# IOs.net
KiCad netlist of a schematic drawn in Altium Designer
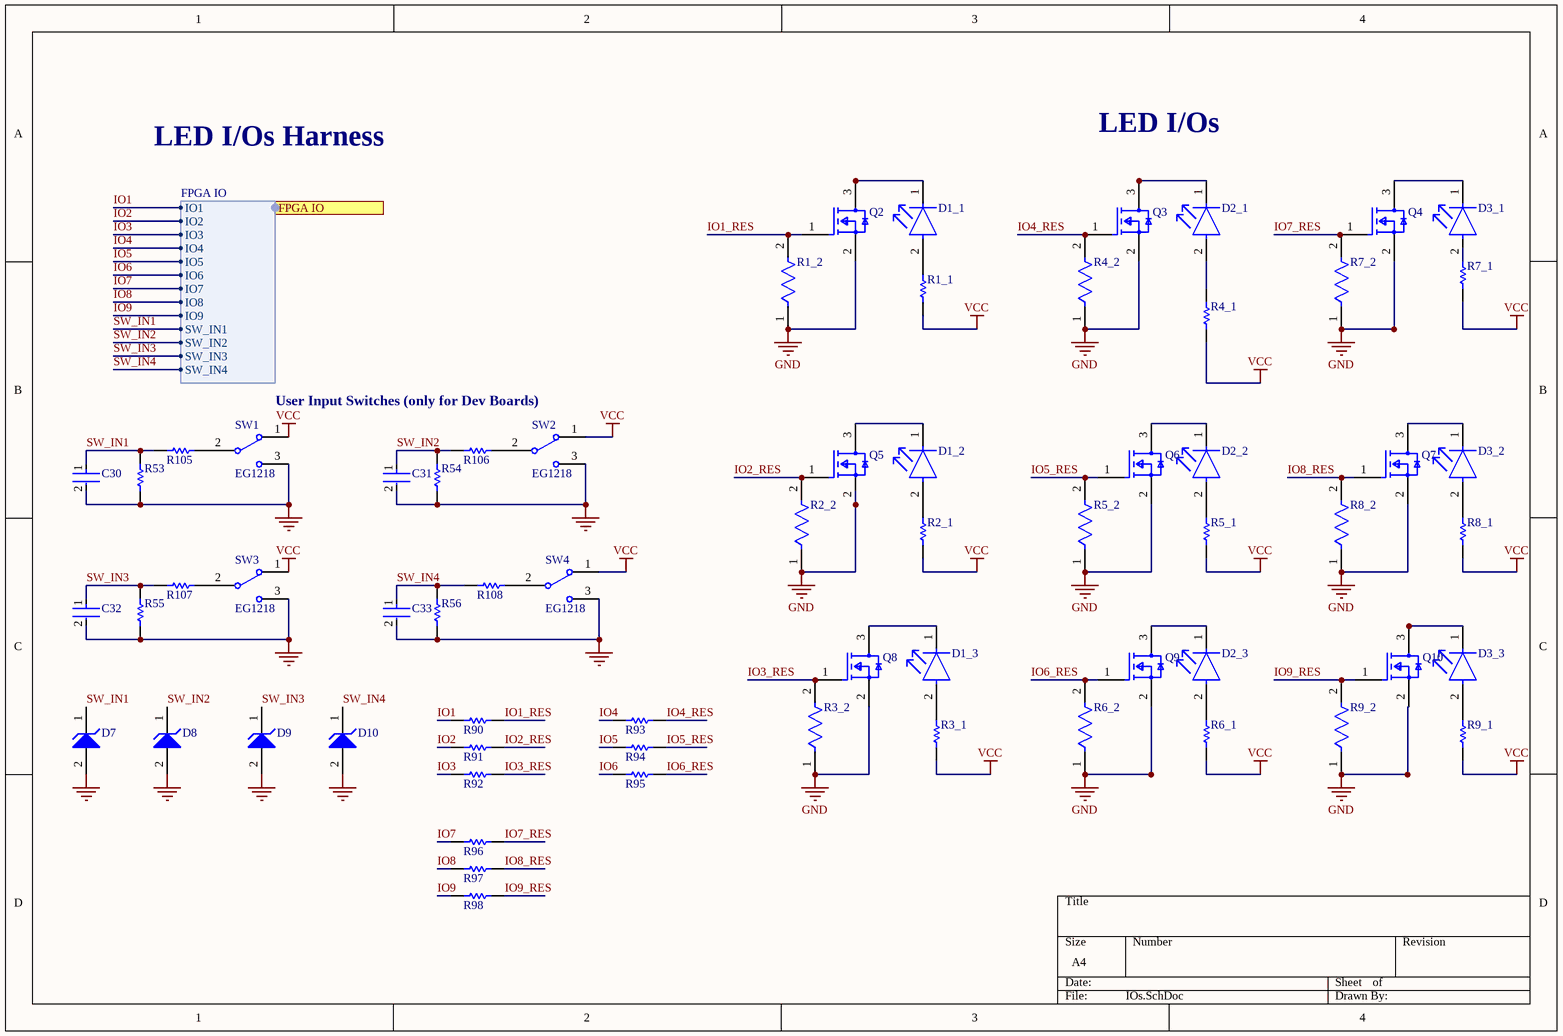
[diagram p0: IOs.SchDoc]

(export (version "E")
  (design (tool "Eeschema 10.0.6"))
  (components
    (comp (ref "C30")
      (value "CC0402KRX7R9BB103")
      (footprint "FP-CC0402-MFG")
      (description "CAP CER 10000PF 50V X7R 0402")
      (fields
        (field (name "OCTOPART") "https://octopart.com/cc0402krx7r9bb103-yageo-8376513")
        (field (name "MANUFACTURER") "YAGEO")
      )
      (libsource (lib "Altium Content Vault") (part "11868f565c42a9108669ba33697ecf6"))
    )
    (comp (ref "C31")
      (value "CC0402KRX7R9BB103")
      (footprint "FP-CC0402-MFG")
      (description "CAP CER 10000PF 50V X7R 0402")
      (fields
        (field (name "OCTOPART") "https://octopart.com/cc0402krx7r9bb103-yageo-8376513")
        (field (name "MANUFACTURER") "YAGEO")
      )
      (libsource (lib "Altium Content Vault") (part "11868f565c42a9108669ba33697ecf6"))
    )
    (comp (ref "C32")
      (value "CC0402KRX7R9BB103")
      (footprint "FP-CC0402-MFG")
      (description "CAP CER 10000PF 50V X7R 0402")
      (fields
        (field (name "OCTOPART") "https://octopart.com/cc0402krx7r9bb103-yageo-8376513")
        (field (name "MANUFACTURER") "YAGEO")
      )
      (libsource (lib "Altium Content Vault") (part "11868f565c42a9108669ba33697ecf6"))
    )
    (comp (ref "C33")
      (value "CC0402KRX7R9BB103")
      (footprint "FP-CC0402-MFG")
      (description "CAP CER 10000PF 50V X7R 0402")
      (fields
        (field (name "OCTOPART") "https://octopart.com/cc0402krx7r9bb103-yageo-8376513")
        (field (name "MANUFACTURER") "YAGEO")
      )
      (libsource (lib "Altium Content Vault") (part "11868f565c42a9108669ba33697ecf6"))
    )
    (comp (ref "D1_1")
      (value "LTST-C230KRKT")
      (footprint "FP-LTST-C230KRKT-MFG")
      (description "LED RED CLEAR CHIP SMD")
      (libsource (lib "Altium Content Vault") (part "8706943c75ba83719d021d2fdc84c58"))
    )
    (comp (ref "D1_2")
      (value "LTST-C230KRKT")
      (footprint "FP-LTST-C230KRKT-MFG")
      (description "LED RED CLEAR CHIP SMD")
      (libsource (lib "Altium Content Vault") (part "8706943c75ba83719d021d2fdc84c58"))
    )
    (comp (ref "D1_3")
      (value "LTST-C230KRKT")
      (footprint "FP-LTST-C230KRKT-MFG")
      (description "LED RED CLEAR CHIP SMD")
      (libsource (lib "Altium Content Vault") (part "8706943c75ba83719d021d2fdc84c58"))
    )
    (comp (ref "D2_1")
      (value "LTST-C230KRKT")
      (footprint "FP-LTST-C230KRKT-MFG")
      (description "LED RED CLEAR CHIP SMD")
      (libsource (lib "Altium Content Vault") (part "8706943c75ba83719d021d2fdc84c58"))
    )
    (comp (ref "D2_2")
      (value "LTST-C230KRKT")
      (footprint "FP-LTST-C230KRKT-MFG")
      (description "LED RED CLEAR CHIP SMD")
      (libsource (lib "Altium Content Vault") (part "8706943c75ba83719d021d2fdc84c58"))
    )
    (comp (ref "D2_3")
      (value "LTST-C230KRKT")
      (footprint "FP-LTST-C230KRKT-MFG")
      (description "LED RED CLEAR CHIP SMD")
      (libsource (lib "Altium Content Vault") (part "8706943c75ba83719d021d2fdc84c58"))
    )
    (comp (ref "D3_1")
      (value "LTST-C230KRKT")
      (footprint "FP-LTST-C230KRKT-MFG")
      (description "LED RED CLEAR CHIP SMD")
      (libsource (lib "Altium Content Vault") (part "8706943c75ba83719d021d2fdc84c58"))
    )
    (comp (ref "D3_2")
      (value "LTST-C230KRKT")
      (footprint "FP-LTST-C230KRKT-MFG")
      (description "LED RED CLEAR CHIP SMD")
      (libsource (lib "Altium Content Vault") (part "8706943c75ba83719d021d2fdc84c58"))
    )
    (comp (ref "D3_3")
      (value "LTST-C230KRKT")
      (footprint "FP-LTST-C230KRKT-MFG")
      (description "LED RED CLEAR CHIP SMD")
      (libsource (lib "Altium Content Vault") (part "8706943c75ba83719d021d2fdc84c58"))
    )
    (comp (ref "D7")
      (value "MM5Z3V3T1G")
      (footprint "ONSC-SOD-523-2-502-01_V")
      (description "Zener Voltage Regulator, 500 mW, 2-Pin SOD-523, Pb-Free, Tape and Reel")
      (fields (field (name "MANUFACTURER") "On Semiconductor"))
      (libsource (lib "Altium Content Vault") (part "ONSC-K1A2-2"))
    )
    (comp (ref "D8")
      (value "MM5Z3V3T1G")
      (footprint "ONSC-SOD-523-2-502-01_V")
      (description "Zener Voltage Regulator, 500 mW, 2-Pin SOD-523, Pb-Free, Tape and Reel")
      (fields (field (name "MANUFACTURER") "On Semiconductor"))
      (libsource (lib "Altium Content Vault") (part "ONSC-K1A2-2"))
    )
    (comp (ref "D9")
      (value "MM5Z3V3T1G")
      (footprint "ONSC-SOD-523-2-502-01_V")
      (description "Zener Voltage Regulator, 500 mW, 2-Pin SOD-523, Pb-Free, Tape and Reel")
      (fields (field (name "MANUFACTURER") "On Semiconductor"))
      (libsource (lib "Altium Content Vault") (part "ONSC-K1A2-2"))
    )
    (comp (ref "D10")
      (value "MM5Z3V3T1G")
      (footprint "ONSC-SOD-523-2-502-01_V")
      (description "Zener Voltage Regulator, 500 mW, 2-Pin SOD-523, Pb-Free, Tape and Reel")
      (fields (field (name "MANUFACTURER") "On Semiconductor"))
      (libsource (lib "Altium Content Vault") (part "ONSC-K1A2-2"))
    )
    (comp (ref "Q2")
      (value "MMBF170LT1G")
      (footprint "FP-318-08-IPC_B")
      (description "MOSFET N-CH 60V 500MA SOT-23")
      (libsource (lib "Altium Content Vault") (part "0a9ea7c96deaaede766a5b531c28de0"))
    )
    (comp (ref "Q3")
      (value "MMBF170LT1G")
      (footprint "FP-318-08-IPC_B")
      (description "MOSFET N-CH 60V 500MA SOT-23")
      (libsource (lib "Altium Content Vault") (part "0a9ea7c96deaaede766a5b531c28de0"))
    )
    (comp (ref "Q4")
      (value "MMBF170LT1G")
      (footprint "FP-318-08-IPC_B")
      (description "MOSFET N-CH 60V 500MA SOT-23")
      (libsource (lib "Altium Content Vault") (part "0a9ea7c96deaaede766a5b531c28de0"))
    )
    (comp (ref "Q5")
      (value "MMBF170LT1G")
      (footprint "FP-318-08-IPC_B")
      (description "MOSFET N-CH 60V 500MA SOT-23")
      (libsource (lib "Altium Content Vault") (part "0a9ea7c96deaaede766a5b531c28de0"))
    )
    (comp (ref "Q6")
      (value "MMBF170LT1G")
      (footprint "FP-318-08-IPC_B")
      (description "MOSFET N-CH 60V 500MA SOT-23")
      (libsource (lib "Altium Content Vault") (part "0a9ea7c96deaaede766a5b531c28de0"))
    )
    (comp (ref "Q7")
      (value "MMBF170LT1G")
      (footprint "FP-318-08-IPC_B")
      (description "MOSFET N-CH 60V 500MA SOT-23")
      (libsource (lib "Altium Content Vault") (part "0a9ea7c96deaaede766a5b531c28de0"))
    )
    (comp (ref "Q8")
      (value "MMBF170LT1G")
      (footprint "FP-318-08-IPC_B")
      (description "MOSFET N-CH 60V 500MA SOT-23")
      (libsource (lib "Altium Content Vault") (part "0a9ea7c96deaaede766a5b531c28de0"))
    )
    (comp (ref "Q9")
      (value "MMBF170LT1G")
      (footprint "FP-318-08-IPC_B")
      (description "MOSFET N-CH 60V 500MA SOT-23")
      (libsource (lib "Altium Content Vault") (part "0a9ea7c96deaaede766a5b531c28de0"))
    )
    (comp (ref "Q10")
      (value "MMBF170LT1G")
      (footprint "FP-318-08-IPC_B")
      (description "MOSFET N-CH 60V 500MA SOT-23")
      (libsource (lib "Altium Content Vault") (part "0a9ea7c96deaaede766a5b531c28de0"))
    )
    (comp (ref "R1_1")
      (value "RC0402FR-07330RL")
      (footprint "RESC1005X40X25LL05T10")
      (fields (field (name "MANUFACTURER") "Yageo / Phycomp"))
      (libsource (lib "Altium Content Vault") (part "RES"))
    )
    (comp (ref "R1_2")
      (value "RC0402JR-0710KL")
      (footprint "FP-RC0402-0_4-IPC_C")
      (description "RES 10K OHM 5% 1/16W 0402")
      (fields (field (name "TOLERANCE") "5%"))
      (libsource (lib "Altium Content Vault") (part "1029c3af85768c4190bb7ad29bc67b5"))
    )
    (comp (ref "R2_1")
      (value "RC0402FR-07330RL")
      (footprint "RESC1005X40X25LL05T10")
      (fields (field (name "MANUFACTURER") "Yageo / Phycomp"))
      (libsource (lib "Altium Content Vault") (part "RES"))
    )
    (comp (ref "R2_2")
      (value "RC0402JR-0710KL")
      (footprint "FP-RC0402-0_4-IPC_C")
      (description "RES 10K OHM 5% 1/16W 0402")
      (fields (field (name "TOLERANCE") "5%"))
      (libsource (lib "Altium Content Vault") (part "1029c3af85768c4190bb7ad29bc67b5"))
    )
    (comp (ref "R3_1")
      (value "RC0402FR-07330RL")
      (footprint "RESC1005X40X25LL05T10")
      (fields (field (name "MANUFACTURER") "Yageo / Phycomp"))
      (libsource (lib "Altium Content Vault") (part "RES"))
    )
    (comp (ref "R3_2")
      (value "RC0402JR-0710KL")
      (footprint "FP-RC0402-0_4-IPC_C")
      (description "RES 10K OHM 5% 1/16W 0402")
      (fields (field (name "TOLERANCE") "5%"))
      (libsource (lib "Altium Content Vault") (part "1029c3af85768c4190bb7ad29bc67b5"))
    )
    (comp (ref "R4_1")
      (value "RC0402FR-07330RL")
      (footprint "RESC1005X40X25LL05T10")
      (fields (field (name "MANUFACTURER") "Yageo / Phycomp"))
      (libsource (lib "Altium Content Vault") (part "RES"))
    )
    (comp (ref "R4_2")
      (value "RC0402JR-0710KL")
      (footprint "FP-RC0402-0_4-IPC_C")
      (description "RES 10K OHM 5% 1/16W 0402")
      (fields (field (name "TOLERANCE") "5%"))
      (libsource (lib "Altium Content Vault") (part "1029c3af85768c4190bb7ad29bc67b5"))
    )
    (comp (ref "R5_1")
      (value "RC0402FR-07330RL")
      (footprint "RESC1005X40X25LL05T10")
      (fields (field (name "MANUFACTURER") "Yageo / Phycomp"))
      (libsource (lib "Altium Content Vault") (part "RES"))
    )
    (comp (ref "R5_2")
      (value "RC0402JR-0710KL")
      (footprint "FP-RC0402-0_4-IPC_C")
      (description "RES 10K OHM 5% 1/16W 0402")
      (fields (field (name "TOLERANCE") "5%"))
      (libsource (lib "Altium Content Vault") (part "1029c3af85768c4190bb7ad29bc67b5"))
    )
    (comp (ref "R6_1")
      (value "RC0402FR-07330RL")
      (footprint "RESC1005X40X25LL05T10")
      (fields (field (name "MANUFACTURER") "Yageo / Phycomp"))
      (libsource (lib "Altium Content Vault") (part "RES"))
    )
    (comp (ref "R6_2")
      (value "RC0402JR-0710KL")
      (footprint "FP-RC0402-0_4-IPC_C")
      (description "RES 10K OHM 5% 1/16W 0402")
      (fields (field (name "TOLERANCE") "5%"))
      (libsource (lib "Altium Content Vault") (part "1029c3af85768c4190bb7ad29bc67b5"))
    )
    (comp (ref "R7_1")
      (value "RC0402FR-07330RL")
      (footprint "RESC1005X40X25LL05T10")
      (fields (field (name "MANUFACTURER") "Yageo / Phycomp"))
      (libsource (lib "Altium Content Vault") (part "RES"))
    )
    (comp (ref "R7_2")
      (value "RC0402JR-0710KL")
      (footprint "FP-RC0402-0_4-IPC_C")
      (description "RES 10K OHM 5% 1/16W 0402")
      (fields (field (name "TOLERANCE") "5%"))
      (libsource (lib "Altium Content Vault") (part "1029c3af85768c4190bb7ad29bc67b5"))
    )
    (comp (ref "R8_1")
      (value "RC0402FR-07330RL")
      (footprint "RESC1005X40X25LL05T10")
      (fields (field (name "MANUFACTURER") "Yageo / Phycomp"))
      (libsource (lib "Altium Content Vault") (part "RES"))
    )
    (comp (ref "R8_2")
      (value "RC0402JR-0710KL")
      (footprint "FP-RC0402-0_4-IPC_C")
      (description "RES 10K OHM 5% 1/16W 0402")
      (fields (field (name "TOLERANCE") "5%"))
      (libsource (lib "Altium Content Vault") (part "1029c3af85768c4190bb7ad29bc67b5"))
    )
    (comp (ref "R9_1")
      (value "RC0402FR-07330RL")
      (footprint "RESC1005X40X25LL05T10")
      (fields (field (name "MANUFACTURER") "Yageo / Phycomp"))
      (libsource (lib "Altium Content Vault") (part "RES"))
    )
    (comp (ref "R9_2")
      (value "RC0402JR-0710KL")
      (footprint "FP-RC0402-0_4-IPC_C")
      (description "RES 10K OHM 5% 1/16W 0402")
      (fields (field (name "TOLERANCE") "5%"))
      (libsource (lib "Altium Content Vault") (part "1029c3af85768c4190bb7ad29bc67b5"))
    )
    (comp (ref "R53")
      (value "3K3 5% 0603(1608)")
      (footprint "RESC0603(1608)_N")
      (description "3K3 0.1W 5% 0603 (1608 Metric)  SMD")
      (fields (field (name "TOLERANCE") "5 %") (field (name "POWER") "0.1 W"))
      (libsource (lib "Altium Content Vault") (part "RES"))
    )
    (comp (ref "R54")
      (value "3K3 5% 0603(1608)")
      (footprint "RESC0603(1608)_N")
      (description "3K3 0.1W 5% 0603 (1608 Metric)  SMD")
      (fields (field (name "TOLERANCE") "5 %") (field (name "POWER") "0.1 W"))
      (libsource (lib "Altium Content Vault") (part "RES"))
    )
    (comp (ref "R55")
      (value "3K3 5% 0603(1608)")
      (footprint "RESC0603(1608)_N")
      (description "3K3 0.1W 5% 0603 (1608 Metric)  SMD")
      (fields (field (name "TOLERANCE") "5 %") (field (name "POWER") "0.1 W"))
      (libsource (lib "Altium Content Vault") (part "RES"))
    )
    (comp (ref "R56")
      (value "3K3 5% 0603(1608)")
      (footprint "RESC0603(1608)_N")
      (description "3K3 0.1W 5% 0603 (1608 Metric)  SMD")
      (fields (field (name "TOLERANCE") "5 %") (field (name "POWER") "0.1 W"))
      (libsource (lib "Altium Content Vault") (part "RES"))
    )
    (comp (ref "R90")
      (value "RC0402FR-07330RL")
      (footprint "RESC1005X40X25LL05T10")
      (fields (field (name "MANUFACTURER") "Yageo / Phycomp"))
      (libsource (lib "Altium Content Vault") (part "RES"))
    )
    (comp (ref "R91")
      (value "RC0402FR-07330RL")
      (footprint "RESC1005X40X25LL05T10")
      (fields (field (name "MANUFACTURER") "Yageo / Phycomp"))
      (libsource (lib "Altium Content Vault") (part "RES"))
    )
    (comp (ref "R92")
      (value "RC0402FR-07330RL")
      (footprint "RESC1005X40X25LL05T10")
      (fields (field (name "MANUFACTURER") "Yageo / Phycomp"))
      (libsource (lib "Altium Content Vault") (part "RES"))
    )
    (comp (ref "R93")
      (value "RC0402FR-07330RL")
      (footprint "RESC1005X40X25LL05T10")
      (fields (field (name "MANUFACTURER") "Yageo / Phycomp"))
      (libsource (lib "Altium Content Vault") (part "RES"))
    )
    (comp (ref "R94")
      (value "RC0402FR-07330RL")
      (footprint "RESC1005X40X25LL05T10")
      (fields (field (name "MANUFACTURER") "Yageo / Phycomp"))
      (libsource (lib "Altium Content Vault") (part "RES"))
    )
    (comp (ref "R95")
      (value "RC0402FR-07330RL")
      (footprint "RESC1005X40X25LL05T10")
      (fields (field (name "MANUFACTURER") "Yageo / Phycomp"))
      (libsource (lib "Altium Content Vault") (part "RES"))
    )
    (comp (ref "R96")
      (value "RC0402FR-07330RL")
      (footprint "RESC1005X40X25LL05T10")
      (fields (field (name "MANUFACTURER") "Yageo / Phycomp"))
      (libsource (lib "Altium Content Vault") (part "RES"))
    )
    (comp (ref "R97")
      (value "RC0402FR-07330RL")
      (footprint "RESC1005X40X25LL05T10")
      (fields (field (name "MANUFACTURER") "Yageo / Phycomp"))
      (libsource (lib "Altium Content Vault") (part "RES"))
    )
    (comp (ref "R98")
      (value "RC0402FR-07330RL")
      (footprint "RESC1005X40X25LL05T10")
      (fields (field (name "MANUFACTURER") "Yageo / Phycomp"))
      (libsource (lib "Altium Content Vault") (part "RES"))
    )
    (comp (ref "R105")
      (value "RC0402FR-07330RL")
      (footprint "RESC1005X40X25LL05T10")
      (fields (field (name "MANUFACTURER") "Yageo / Phycomp"))
      (libsource (lib "Altium Content Vault") (part "RES"))
    )
    (comp (ref "R106")
      (value "RC0402FR-07330RL")
      (footprint "RESC1005X40X25LL05T10")
      (fields (field (name "MANUFACTURER") "Yageo / Phycomp"))
      (libsource (lib "Altium Content Vault") (part "RES"))
    )
    (comp (ref "R107")
      (value "RC0402FR-07330RL")
      (footprint "RESC1005X40X25LL05T10")
      (fields (field (name "MANUFACTURER") "Yageo / Phycomp"))
      (libsource (lib "Altium Content Vault") (part "RES"))
    )
    (comp (ref "R108")
      (value "RC0402FR-07330RL")
      (footprint "RESC1005X40X25LL05T10")
      (fields (field (name "MANUFACTURER") "Yageo / Phycomp"))
      (libsource (lib "Altium Content Vault") (part "RES"))
    )
    (comp (ref "SW1")
      (value "EG1218")
      (footprint "ESWI-EG1218_V")
      (description "Slide Switch, 500 V, -20 to 70 degC, 3-Pin THD, RoHS")
      (libsource (lib "Altium Content Vault") (part "SW-SPDT-3_B"))
    )
    (comp (ref "SW2")
      (value "EG1218")
      (footprint "ESWI-EG1218_V")
      (description "Slide Switch, 500 V, -20 to 70 degC, 3-Pin THD, RoHS")
      (libsource (lib "Altium Content Vault") (part "SW-SPDT-3_B"))
    )
    (comp (ref "SW3")
      (value "EG1218")
      (footprint "ESWI-EG1218_V")
      (description "Slide Switch, 500 V, -20 to 70 degC, 3-Pin THD, RoHS")
      (libsource (lib "Altium Content Vault") (part "SW-SPDT-3_B"))
    )
    (comp (ref "SW4")
      (value "EG1218")
      (footprint "ESWI-EG1218_V")
      (description "Slide Switch, 500 V, -20 to 70 degC, 3-Pin THD, RoHS")
      (libsource (lib "Altium Content Vault") (part "SW-SPDT-3_B"))
    )
  )
  (nets
    (net (code "3") (name "/IO1") (class "Default")
      (node (ref "R90") (pin "2") (pinfunction "2_2") (pintype "passive"))
    )
    (net (code "4") (name "/IO1_RES") (class "Default")
      (node (ref "Q2") (pin "1") (pinfunction "G_1") (pintype "passive"))
      (node (ref "R1_2") (pin "2") (pinfunction "2_2") (pintype "passive"))
      (node (ref "R90") (pin "1") (pinfunction "1_1") (pintype "passive"))
    )
    (net (code "5") (name "/IO2") (class "Default")
      (node (ref "R91") (pin "2") (pinfunction "2_2") (pintype "passive"))
    )
    (net (code "6") (name "/IO2_RES") (class "Default")
      (node (ref "Q5") (pin "1") (pinfunction "G_1") (pintype "passive"))
      (node (ref "R2_2") (pin "2") (pinfunction "2_2") (pintype "passive"))
      (node (ref "R91") (pin "1") (pinfunction "1_1") (pintype "passive"))
    )
    (net (code "7") (name "/IO3") (class "Default")
      (node (ref "R92") (pin "2") (pinfunction "2_2") (pintype "passive"))
    )
    (net (code "8") (name "/IO3_RES") (class "Default")
      (node (ref "Q8") (pin "1") (pinfunction "G_1") (pintype "passive"))
      (node (ref "R3_2") (pin "2") (pinfunction "2_2") (pintype "passive"))
      (node (ref "R92") (pin "1") (pinfunction "1_1") (pintype "passive"))
    )
    (net (code "9") (name "/IO4") (class "Default")
      (node (ref "R93") (pin "2") (pinfunction "2_2") (pintype "passive"))
    )
    (net (code "10") (name "/IO4_RES") (class "Default")
      (node (ref "Q3") (pin "1") (pinfunction "G_1") (pintype "passive"))
      (node (ref "R4_2") (pin "2") (pinfunction "2_2") (pintype "passive"))
      (node (ref "R93") (pin "1") (pinfunction "1_1") (pintype "passive"))
    )
    (net (code "11") (name "/IO5") (class "Default")
      (node (ref "R94") (pin "2") (pinfunction "2_2") (pintype "passive"))
    )
    (net (code "12") (name "/IO5_RES") (class "Default")
      (node (ref "Q6") (pin "1") (pinfunction "G_1") (pintype "passive"))
      (node (ref "R5_2") (pin "2") (pinfunction "2_2") (pintype "passive"))
      (node (ref "R94") (pin "1") (pinfunction "1_1") (pintype "passive"))
    )
    (net (code "13") (name "/IO6") (class "Default")
      (node (ref "R95") (pin "2") (pinfunction "2_2") (pintype "passive"))
    )
    (net (code "14") (name "/IO6_RES") (class "Default")
      (node (ref "Q9") (pin "1") (pinfunction "G_1") (pintype "passive"))
      (node (ref "R6_2") (pin "2") (pinfunction "2_2") (pintype "passive"))
      (node (ref "R95") (pin "1") (pinfunction "1_1") (pintype "passive"))
    )
    (net (code "15") (name "/IO7") (class "Default")
      (node (ref "R96") (pin "2") (pinfunction "2_2") (pintype "passive"))
    )
    (net (code "16") (name "/IO7_RES") (class "Default")
      (node (ref "Q4") (pin "1") (pinfunction "G_1") (pintype "passive"))
      (node (ref "R7_2") (pin "2") (pinfunction "2_2") (pintype "passive"))
      (node (ref "R96") (pin "1") (pinfunction "1_1") (pintype "passive"))
    )
    (net (code "17") (name "/IO8") (class "Default")
      (node (ref "R97") (pin "2") (pinfunction "2_2") (pintype "passive"))
    )
    (net (code "18") (name "/IO8_RES") (class "Default")
      (node (ref "Q7") (pin "1") (pinfunction "G_1") (pintype "passive"))
      (node (ref "R8_2") (pin "2") (pinfunction "2_2") (pintype "passive"))
      (node (ref "R97") (pin "1") (pinfunction "1_1") (pintype "passive"))
    )
    (net (code "19") (name "/IO9") (class "Default")
      (node (ref "R98") (pin "2") (pinfunction "2_2") (pintype "passive"))
    )
    (net (code "20") (name "/IO9_RES") (class "Default")
      (node (ref "Q10") (pin "1") (pinfunction "G_1") (pintype "passive"))
      (node (ref "R98") (pin "1") (pinfunction "1_1") (pintype "passive"))
      (node (ref "R9_2") (pin "2") (pinfunction "2_2") (pintype "passive"))
    )
    (net (code "21") (name "/SW_IN1") (class "Default")
      (node (ref "C30") (pin "1") (pinfunction "1_1") (pintype "passive"))
      (node (ref "D7") (pin "1") (pinfunction "K_1") (pintype "passive"))
      (node (ref "R105") (pin "2") (pinfunction "2_2") (pintype "passive"))
      (node (ref "R53") (pin "2") (pinfunction "2_2") (pintype "passive"))
    )
    (net (code "22") (name "/SW_IN2") (class "Default")
      (node (ref "C31") (pin "1") (pinfunction "1_1") (pintype "passive"))
      (node (ref "D8") (pin "1") (pinfunction "K_1") (pintype "passive"))
      (node (ref "R106") (pin "2") (pinfunction "2_2") (pintype "passive"))
      (node (ref "R54") (pin "2") (pinfunction "2_2") (pintype "passive"))
    )
    (net (code "23") (name "/SW_IN3") (class "Default")
      (node (ref "C32") (pin "1") (pinfunction "1_1") (pintype "passive"))
      (node (ref "D9") (pin "1") (pinfunction "K_1") (pintype "passive"))
      (node (ref "R107") (pin "2") (pinfunction "2_2") (pintype "passive"))
      (node (ref "R55") (pin "2") (pinfunction "2_2") (pintype "passive"))
    )
    (net (code "24") (name "/SW_IN4") (class "Default")
      (node (ref "C33") (pin "1") (pinfunction "1_1") (pintype "passive"))
      (node (ref "D10") (pin "1") (pinfunction "K_1") (pintype "passive"))
      (node (ref "R108") (pin "2") (pinfunction "2_2") (pintype "passive"))
      (node (ref "R56") (pin "2") (pinfunction "2_2") (pintype "passive"))
    )
    (net (code "26") (name "GND") (class "Default")
      (node (ref "C30") (pin "2") (pinfunction "2_2") (pintype "passive"))
      (node (ref "C31") (pin "2") (pinfunction "2_2") (pintype "passive"))
      (node (ref "C32") (pin "2") (pinfunction "2_2") (pintype "passive"))
      (node (ref "C33") (pin "2") (pinfunction "2_2") (pintype "passive"))
      (node (ref "D10") (pin "2") (pinfunction "A_2") (pintype "passive"))
      (node (ref "D7") (pin "2") (pinfunction "A_2") (pintype "passive"))
      (node (ref "D8") (pin "2") (pinfunction "A_2") (pintype "passive"))
      (node (ref "D9") (pin "2") (pinfunction "A_2") (pintype "passive"))
      (node (ref "Q10") (pin "2") (pinfunction "S_2") (pintype "passive"))
      (node (ref "Q2") (pin "2") (pinfunction "S_2") (pintype "passive"))
      (node (ref "Q3") (pin "2") (pinfunction "S_2") (pintype "passive"))
      (node (ref "Q4") (pin "2") (pinfunction "S_2") (pintype "passive"))
      (node (ref "Q5") (pin "2") (pinfunction "S_2") (pintype "passive"))
      (node (ref "Q6") (pin "2") (pinfunction "S_2") (pintype "passive"))
      (node (ref "Q7") (pin "2") (pinfunction "S_2") (pintype "passive"))
      (node (ref "Q8") (pin "2") (pinfunction "S_2") (pintype "passive"))
      (node (ref "Q9") (pin "2") (pinfunction "S_2") (pintype "passive"))
      (node (ref "R1_2") (pin "1") (pinfunction "1_1") (pintype "passive"))
      (node (ref "R2_2") (pin "1") (pinfunction "1_1") (pintype "passive"))
      (node (ref "R3_2") (pin "1") (pinfunction "1_1") (pintype "passive"))
      (node (ref "R4_2") (pin "1") (pinfunction "1_1") (pintype "passive"))
      (node (ref "R53") (pin "1") (pinfunction "1_1") (pintype "passive"))
      (node (ref "R54") (pin "1") (pinfunction "1_1") (pintype "passive"))
      (node (ref "R55") (pin "1") (pinfunction "1_1") (pintype "passive"))
      (node (ref "R56") (pin "1") (pinfunction "1_1") (pintype "passive"))
      (node (ref "R5_2") (pin "1") (pinfunction "1_1") (pintype "passive"))
      (node (ref "R6_2") (pin "1") (pinfunction "1_1") (pintype "passive"))
      (node (ref "R7_2") (pin "1") (pinfunction "1_1") (pintype "passive"))
      (node (ref "R8_2") (pin "1") (pinfunction "1_1") (pintype "passive"))
      (node (ref "R9_2") (pin "1") (pinfunction "1_1") (pintype "passive"))
      (node (ref "SW1") (pin "3") (pinfunction "3_3") (pintype "passive"))
      (node (ref "SW2") (pin "3") (pinfunction "3_3") (pintype "passive"))
      (node (ref "SW3") (pin "3") (pinfunction "3_3") (pintype "passive"))
      (node (ref "SW4") (pin "3") (pinfunction "3_3") (pintype "passive"))
    )
    (net (code "27") (name "Net-(D1_1-A)") (class "Default")
      (node (ref "D1_1") (pin "2") (pinfunction "A_2") (pintype "passive"))
      (node (ref "R1_1") (pin "2") (pinfunction "2_2") (pintype "passive"))
    )
    (net (code "28") (name "Net-(D1_1-C)") (class "Default")
      (node (ref "D1_1") (pin "1") (pinfunction "C_1") (pintype "passive"))
      (node (ref "Q2") (pin "3") (pinfunction "D_3") (pintype "passive"))
    )
    (net (code "29") (name "Net-(D1_2-A)") (class "Default")
      (node (ref "D1_2") (pin "2") (pinfunction "A_2") (pintype "passive"))
      (node (ref "R2_1") (pin "2") (pinfunction "2_2") (pintype "passive"))
    )
    (net (code "30") (name "Net-(D1_2-C)") (class "Default")
      (node (ref "D1_2") (pin "1") (pinfunction "C_1") (pintype "passive"))
      (node (ref "Q5") (pin "3") (pinfunction "D_3") (pintype "passive"))
    )
    (net (code "31") (name "Net-(D1_3-A)") (class "Default")
      (node (ref "D1_3") (pin "2") (pinfunction "A_2") (pintype "passive"))
      (node (ref "R3_1") (pin "2") (pinfunction "2_2") (pintype "passive"))
    )
    (net (code "32") (name "Net-(D1_3-C)") (class "Default")
      (node (ref "D1_3") (pin "1") (pinfunction "C_1") (pintype "passive"))
      (node (ref "Q8") (pin "3") (pinfunction "D_3") (pintype "passive"))
    )
    (net (code "33") (name "Net-(D2_1-A)") (class "Default")
      (node (ref "D2_1") (pin "2") (pinfunction "A_2") (pintype "passive"))
      (node (ref "R4_1") (pin "2") (pinfunction "2_2") (pintype "passive"))
    )
    (net (code "34") (name "Net-(D2_1-C)") (class "Default")
      (node (ref "D2_1") (pin "1") (pinfunction "C_1") (pintype "passive"))
      (node (ref "Q3") (pin "3") (pinfunction "D_3") (pintype "passive"))
    )
    (net (code "35") (name "Net-(D2_2-A)") (class "Default")
      (node (ref "D2_2") (pin "2") (pinfunction "A_2") (pintype "passive"))
      (node (ref "R5_1") (pin "2") (pinfunction "2_2") (pintype "passive"))
    )
    (net (code "36") (name "Net-(D2_2-C)") (class "Default")
      (node (ref "D2_2") (pin "1") (pinfunction "C_1") (pintype "passive"))
      (node (ref "Q6") (pin "3") (pinfunction "D_3") (pintype "passive"))
    )
    (net (code "37") (name "Net-(D2_3-A)") (class "Default")
      (node (ref "D2_3") (pin "2") (pinfunction "A_2") (pintype "passive"))
      (node (ref "R6_1") (pin "2") (pinfunction "2_2") (pintype "passive"))
    )
    (net (code "38") (name "Net-(D2_3-C)") (class "Default")
      (node (ref "D2_3") (pin "1") (pinfunction "C_1") (pintype "passive"))
      (node (ref "Q9") (pin "3") (pinfunction "D_3") (pintype "passive"))
    )
    (net (code "39") (name "Net-(D3_1-A)") (class "Default")
      (node (ref "D3_1") (pin "2") (pinfunction "A_2") (pintype "passive"))
      (node (ref "R7_1") (pin "2") (pinfunction "2_2") (pintype "passive"))
    )
    (net (code "40") (name "Net-(D3_1-C)") (class "Default")
      (node (ref "D3_1") (pin "1") (pinfunction "C_1") (pintype "passive"))
      (node (ref "Q4") (pin "3") (pinfunction "D_3") (pintype "passive"))
    )
    (net (code "41") (name "Net-(D3_2-A)") (class "Default")
      (node (ref "D3_2") (pin "2") (pinfunction "A_2") (pintype "passive"))
      (node (ref "R8_1") (pin "2") (pinfunction "2_2") (pintype "passive"))
    )
    (net (code "42") (name "Net-(D3_2-C)") (class "Default")
      (node (ref "D3_2") (pin "1") (pinfunction "C_1") (pintype "passive"))
      (node (ref "Q7") (pin "3") (pinfunction "D_3") (pintype "passive"))
    )
    (net (code "43") (name "Net-(D3_3-A)") (class "Default")
      (node (ref "D3_3") (pin "2") (pinfunction "A_2") (pintype "passive"))
      (node (ref "R9_1") (pin "2") (pinfunction "2_2") (pintype "passive"))
    )
    (net (code "44") (name "Net-(D3_3-C)") (class "Default")
      (node (ref "D3_3") (pin "1") (pinfunction "C_1") (pintype "passive"))
      (node (ref "Q10") (pin "3") (pinfunction "D_3") (pintype "passive"))
    )
    (net (code "45") (name "Net-(SW1-COM)") (class "Default")
      (node (ref "R105") (pin "1") (pinfunction "1_1") (pintype "passive"))
      (node (ref "SW1") (pin "2") (pinfunction "COM_2") (pintype "passive"))
    )
    (net (code "46") (name "Net-(SW2-COM)") (class "Default")
      (node (ref "R106") (pin "1") (pinfunction "1_1") (pintype "passive"))
      (node (ref "SW2") (pin "2") (pinfunction "COM_2") (pintype "passive"))
    )
    (net (code "47") (name "Net-(SW3-COM)") (class "Default")
      (node (ref "R107") (pin "1") (pinfunction "1_1") (pintype "passive"))
      (node (ref "SW3") (pin "2") (pinfunction "COM_2") (pintype "passive"))
    )
    (net (code "48") (name "Net-(SW4-COM)") (class "Default")
      (node (ref "R108") (pin "1") (pinfunction "1_1") (pintype "passive"))
      (node (ref "SW4") (pin "2") (pinfunction "COM_2") (pintype "passive"))
    )
    (net (code "49") (name "VCC") (class "Default")
      (node (ref "R1_1") (pin "1") (pinfunction "1_1") (pintype "passive"))
      (node (ref "R2_1") (pin "1") (pinfunction "1_1") (pintype "passive"))
      (node (ref "R3_1") (pin "1") (pinfunction "1_1") (pintype "passive"))
      (node (ref "R4_1") (pin "1") (pinfunction "1_1") (pintype "passive"))
      (node (ref "R5_1") (pin "1") (pinfunction "1_1") (pintype "passive"))
      (node (ref "R6_1") (pin "1") (pinfunction "1_1") (pintype "passive"))
      (node (ref "R7_1") (pin "1") (pinfunction "1_1") (pintype "passive"))
      (node (ref "R8_1") (pin "1") (pinfunction "1_1") (pintype "passive"))
      (node (ref "R9_1") (pin "1") (pinfunction "1_1") (pintype "passive"))
      (node (ref "SW1") (pin "1") (pinfunction "1_1") (pintype "passive"))
      (node (ref "SW2") (pin "1") (pinfunction "1_1") (pintype "passive"))
      (node (ref "SW3") (pin "1") (pinfunction "1_1") (pintype "passive"))
      (node (ref "SW4") (pin "1") (pinfunction "1_1") (pintype "passive"))
    )
  )
)
